# bs_shield.net
KiCad netlist of a schematic drawn in EAGLE
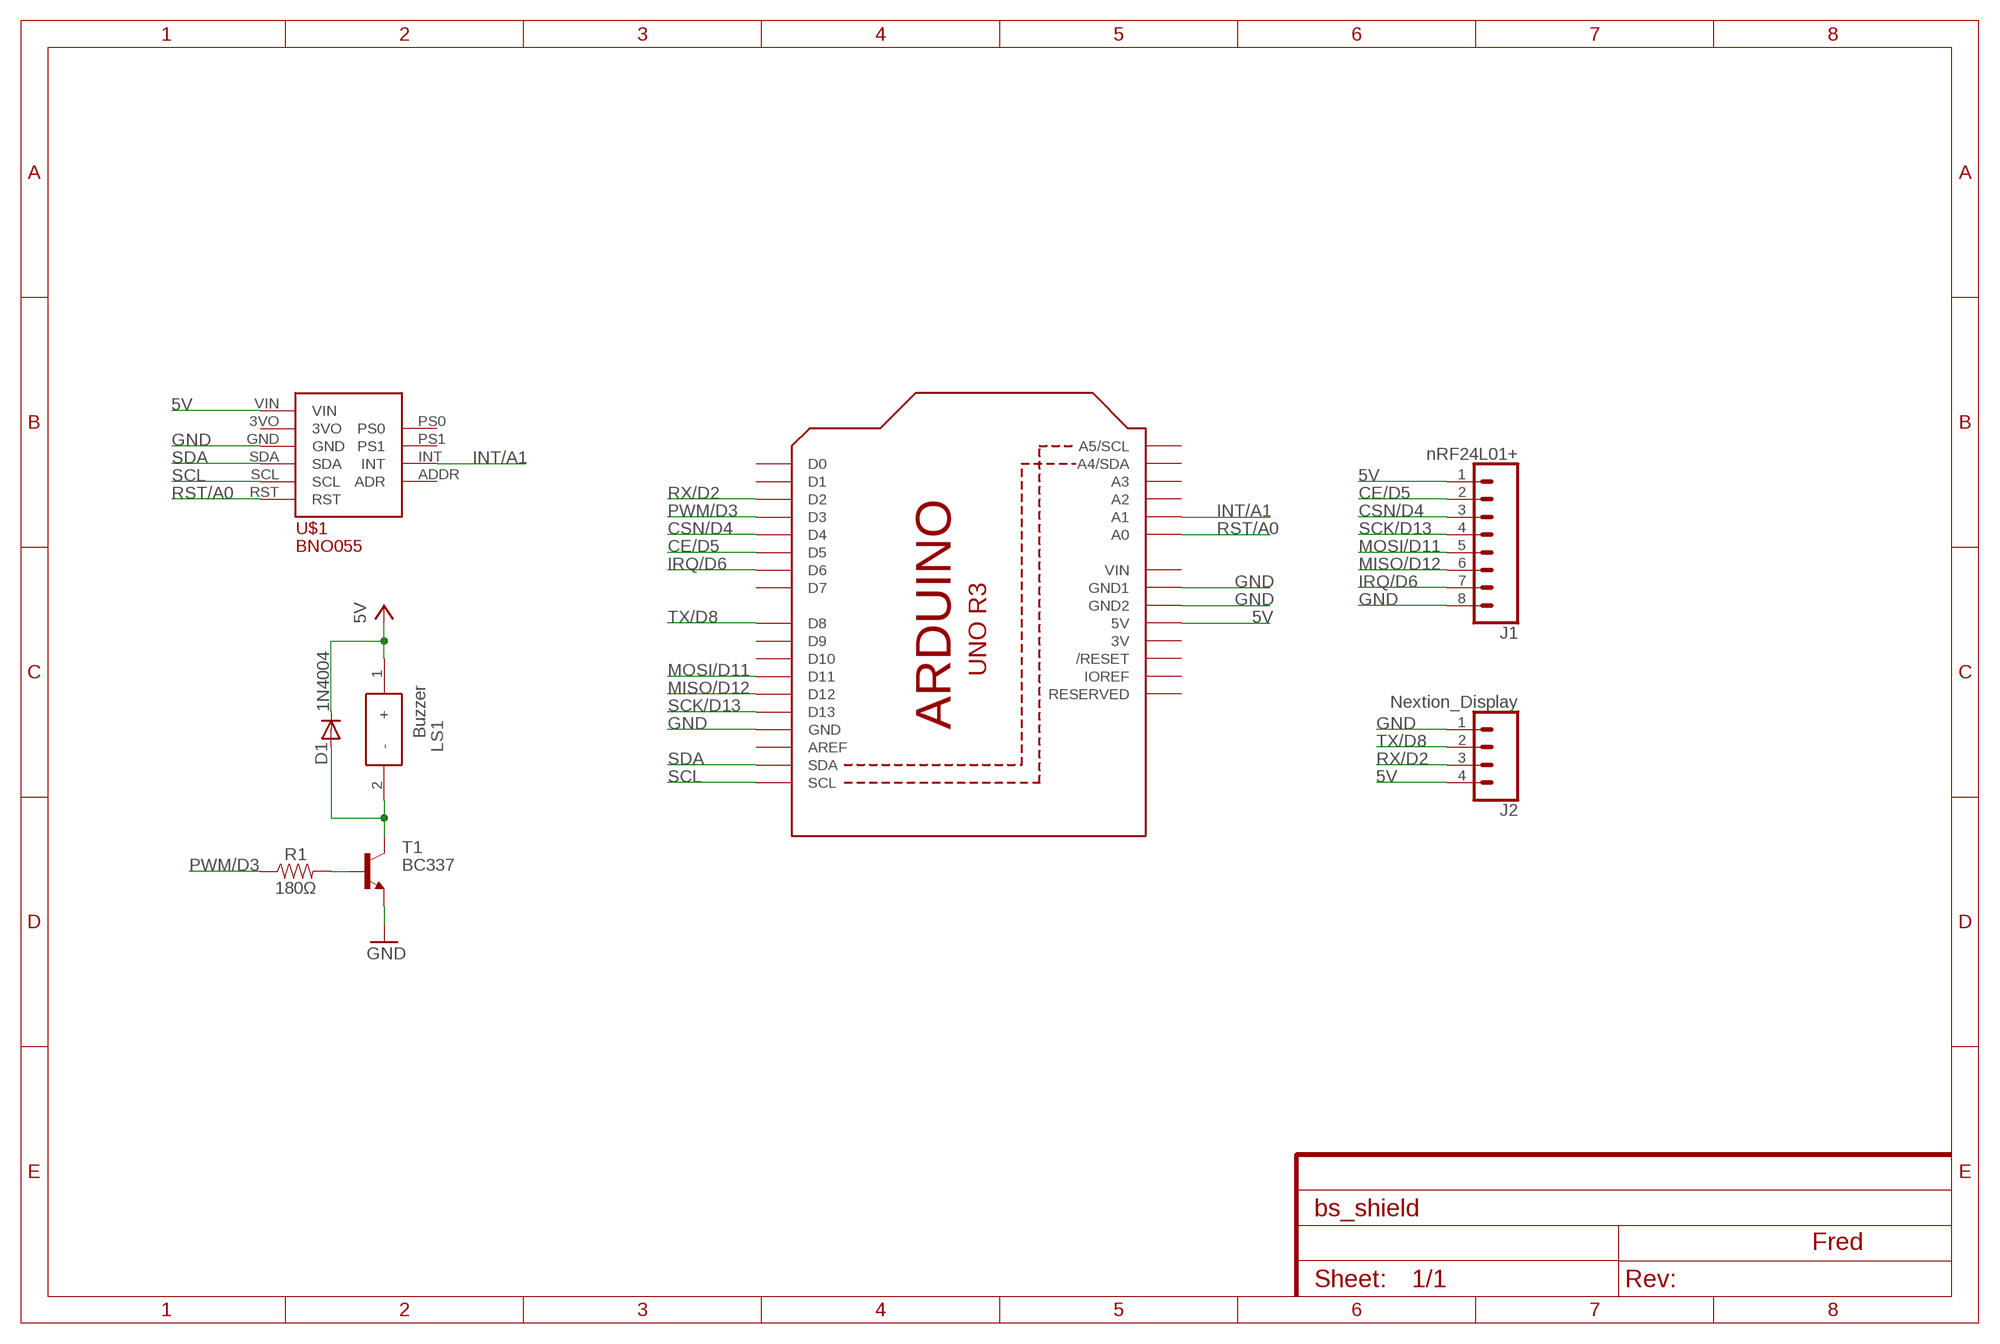
[diagram p0: schematic, sheet 1]

(export (version "E")
  (design (tool "Eeschema 10.0.6"))
  (components
    (comp (ref "D1")
      (value "1N4004")
      (footprint "eagle-import:DO41-10")
      (libsource (lib "eagle-import") (part "1N4004"))
    )
    (comp (ref "J1")
      (value "nRF24L01+")
      (footprint "eagle-import:1X08")
      (libsource (lib "eagle-import") (part "CONN_08{dblquote}"))
    )
    (comp (ref "J2")
      (value "Nextion_Display")
      (footprint "eagle-import:1X04")
      (libsource (lib "eagle-import") (part "CONN_04"))
    )
    (comp (ref "LS1")
      (value "Buzzer")
      (footprint "eagle-import:CEM-1203(42)")
      (fields
        (field (name "MANUFACTURER_PART_NUMBER") "CEM-1203(42)")
        (field (name "MOUSER_PART_NUMBER") "490-CEM-1203(42)")
      )
      (libsource (lib "eagle-import") (part "CEM-1203(42)"))
    )
    (comp (ref "R1")
      (value "180Ω")
      (footprint "eagle-import:AXIAL-0.3")
      (libsource (lib "eagle-import") (part "RESISTORAXIAL-0.3"))
    )
    (comp (ref "T1")
      (value "BC337")
      (footprint "eagle-import:TO92")
      (libsource (lib "eagle-import") (part "BC337"))
    )
    (comp (ref "U$1")
      (value "BNO055")
      (footprint "eagle-import:BB10")
      (libsource (lib "eagle-import") (part "BNO055"))
    )
    (comp (ref "U1")
      (value "ARDUINOR3-DIMENSION")
      (footprint "eagle-import:ARDUINOR3")
      (libsource (lib "eagle-import") (part "ARDUINOR3-DIMENSION"))
    )
  )
  (nets
    (net (code "1") (name "/3V") (class "Default")
      (node (ref "U1") (pin "3V") (pinfunction "3V_3V") (pintype "power_in"))
    )
    (net (code "2") (name "/CE{slash}D5") (class "Default")
      (node (ref "J1") (pin "2") (pinfunction "2_2") (pintype "passive"))
      (node (ref "U1") (pin "D5") (pinfunction "D5_D5") (pintype "bidirectional"))
    )
    (net (code "3") (name "/CSN{slash}D4") (class "Default")
      (node (ref "J1") (pin "3") (pinfunction "3_3") (pintype "passive"))
      (node (ref "U1") (pin "D4") (pinfunction "D4_D4") (pintype "bidirectional"))
    )
    (net (code "4") (name "/INT{slash}A1") (class "Default")
      (node (ref "U$1") (pin "INT") (pinfunction "INT_INT") (pintype "bidirectional"))
      (node (ref "U1") (pin "A1") (pinfunction "A1_A1") (pintype "bidirectional"))
    )
    (net (code "5") (name "/IRQ{slash}D6") (class "Default")
      (node (ref "J1") (pin "7") (pinfunction "7_7") (pintype "passive"))
      (node (ref "U1") (pin "D6") (pinfunction "D6_D6") (pintype "bidirectional"))
    )
    (net (code "6") (name "/MISO{slash}D12") (class "Default")
      (node (ref "J1") (pin "6") (pinfunction "6_6") (pintype "passive"))
      (node (ref "U1") (pin "D12") (pinfunction "D12_D12") (pintype "bidirectional"))
    )
    (net (code "7") (name "/MOSI{slash}D11") (class "Default")
      (node (ref "J1") (pin "5") (pinfunction "5_5") (pintype "passive"))
      (node (ref "U1") (pin "D11") (pinfunction "D11_D11") (pintype "bidirectional"))
    )
    (net (code "8") (name "/PWM{slash}D3") (class "Default")
      (node (ref "R1") (pin "P$1") (pinfunction "1_P$1") (pintype "passive"))
      (node (ref "U1") (pin "D3") (pinfunction "D3_D3") (pintype "bidirectional"))
    )
    (net (code "9") (name "/RST{slash}A0") (class "Default")
      (node (ref "U$1") (pin "RST") (pinfunction "RST_RST") (pintype "bidirectional"))
      (node (ref "U1") (pin "A0") (pinfunction "A0_A0") (pintype "bidirectional"))
    )
    (net (code "10") (name "/RX{slash}D2") (class "Default")
      (node (ref "J2") (pin "3") (pinfunction "3_3") (pintype "passive"))
      (node (ref "U1") (pin "D2") (pinfunction "D2_D2") (pintype "bidirectional"))
    )
    (net (code "11") (name "/SCK{slash}D13") (class "Default")
      (node (ref "J1") (pin "4") (pinfunction "4_4") (pintype "passive"))
      (node (ref "U1") (pin "D13") (pinfunction "D13_D13") (pintype "bidirectional"))
    )
    (net (code "12") (name "/SCL") (class "Default")
      (node (ref "U$1") (pin "SCL") (pinfunction "SCL_SCL") (pintype "bidirectional"))
      (node (ref "U1") (pin "SCL") (pinfunction "SCL_SCL") (pintype "bidirectional"))
    )
    (net (code "13") (name "/SDA") (class "Default")
      (node (ref "U$1") (pin "SDA") (pinfunction "SDA_SDA") (pintype "bidirectional"))
      (node (ref "U1") (pin "SDA") (pinfunction "SDA_SDA") (pintype "bidirectional"))
    )
    (net (code "14") (name "/TX{slash}D8") (class "Default")
      (node (ref "J2") (pin "2") (pinfunction "2_2") (pintype "passive"))
      (node (ref "U1") (pin "D8") (pinfunction "D8_D8") (pintype "bidirectional"))
    )
    (net (code "15") (name "/VIN") (class "Default")
      (node (ref "U1") (pin "VIN") (pinfunction "VIN_VIN") (pintype "power_in"))
    )
    (net (code "16") (name "5V") (class "Default")
      (node (ref "D1") (pin "C") (pinfunction "C_C") (pintype "passive"))
      (node (ref "J1") (pin "1") (pinfunction "1_1") (pintype "passive"))
      (node (ref "J2") (pin "4") (pinfunction "4_4") (pintype "passive"))
      (node (ref "LS1") (pin "1") (pinfunction "+_1") (pintype "bidirectional"))
      (node (ref "U$1") (pin "VIN") (pinfunction "VIN_VIN") (pintype "bidirectional"))
      (node (ref "U1") (pin "5V") (pinfunction "5V_5V") (pintype "power_in"))
    )
    (net (code "17") (name "GND") (class "Default")
      (node (ref "J1") (pin "8") (pinfunction "8_8") (pintype "passive"))
      (node (ref "J2") (pin "1") (pinfunction "1_1") (pintype "passive"))
      (node (ref "T1") (pin "1") (pinfunction "E_1") (pintype "passive"))
      (node (ref "U$1") (pin "GND") (pinfunction "GND_GND") (pintype "bidirectional"))
      (node (ref "U1") (pin "GND") (pinfunction "GND_GND") (pintype "power_in"))
      (node (ref "U1") (pin "GND1") (pinfunction "GND1_GND1") (pintype "power_in"))
      (node (ref "U1") (pin "GND2") (pinfunction "GND2_GND2") (pintype "power_in"))
    )
    (net (code "18") (name "Net-(LS1--)") (class "Default")
      (node (ref "D1") (pin "A") (pinfunction "A_A") (pintype "passive"))
      (node (ref "LS1") (pin "2") (pinfunction "-_2") (pintype "bidirectional"))
      (node (ref "T1") (pin "3") (pinfunction "C_3") (pintype "passive"))
    )
    (net (code "19") (name "Net-(R1-2)") (class "Default")
      (node (ref "R1") (pin "P$2") (pinfunction "2_P$2") (pintype "passive"))
      (node (ref "T1") (pin "2") (pinfunction "B_2") (pintype "passive"))
    )
    (net (code "20") (name "unconnected-(U$1-ADR-PadADDR)") (class "Default")
      (node (ref "U$1") (pin "ADDR") (pinfunction "ADR_ADDR") (pintype "bidirectional"))
    )
    (net (code "21") (name "unconnected-(U$1-Pad3VO)") (class "Default")
      (node (ref "U$1") (pin "3VO") (pinfunction "3VO_3VO") (pintype "bidirectional"))
    )
    (net (code "22") (name "unconnected-(U$1-PadPS0)") (class "Default")
      (node (ref "U$1") (pin "PS0") (pinfunction "PS0_PS0") (pintype "bidirectional"))
    )
    (net (code "23") (name "unconnected-(U$1-PadPS1)") (class "Default")
      (node (ref "U$1") (pin "PS1") (pinfunction "PS1_PS1") (pintype "bidirectional"))
    )
    (net (code "24") (name "unconnected-(U1-A4{slash}SDA-PadA4)") (class "Default")
      (node (ref "U1") (pin "A4") (pinfunction "A4/SDA_A4") (pintype "bidirectional"))
    )
    (net (code "25") (name "unconnected-(U1-A5{slash}SCL-PadA5)") (class "Default")
      (node (ref "U1") (pin "A5") (pinfunction "A5/SCL_A5") (pintype "bidirectional"))
    )
    (net (code "26") (name "unconnected-(U1-PadA2)") (class "Default")
      (node (ref "U1") (pin "A2") (pinfunction "A2_A2") (pintype "bidirectional"))
    )
    (net (code "27") (name "unconnected-(U1-PadA3)") (class "Default")
      (node (ref "U1") (pin "A3") (pinfunction "A3_A3") (pintype "bidirectional"))
    )
    (net (code "28") (name "unconnected-(U1-PadAREF)") (class "Default")
      (node (ref "U1") (pin "AREF") (pinfunction "AREF_AREF") (pintype "bidirectional"))
    )
    (net (code "29") (name "unconnected-(U1-PadD0)") (class "Default")
      (node (ref "U1") (pin "D0") (pinfunction "D0_D0") (pintype "bidirectional"))
    )
    (net (code "30") (name "unconnected-(U1-PadD1)") (class "Default")
      (node (ref "U1") (pin "D1") (pinfunction "D1_D1") (pintype "bidirectional"))
    )
    (net (code "31") (name "unconnected-(U1-PadD7)") (class "Default")
      (node (ref "U1") (pin "D7") (pinfunction "D7_D7") (pintype "bidirectional"))
    )
    (net (code "32") (name "unconnected-(U1-PadD9)") (class "Default")
      (node (ref "U1") (pin "D9") (pinfunction "D9_D9") (pintype "bidirectional"))
    )
    (net (code "33") (name "unconnected-(U1-PadD10)") (class "Default")
      (node (ref "U1") (pin "D10") (pinfunction "D10_D10") (pintype "bidirectional"))
    )
    (net (code "34") (name "unconnected-(U1-PadIOREF)") (class "Default")
      (node (ref "U1") (pin "IOREF") (pinfunction "IOREF_IOREF") (pintype "output"))
    )
    (net (code "35") (name "unconnected-(U1-PadRESERVED)") (class "Default")
      (node (ref "U1") (pin "RESERVED") (pinfunction "RESERVED_RESERVED") (pintype "no_connect"))
    )
    (net (code "36") (name "unconnected-(U1-{slash}RESET-PadRESET)") (class "Default")
      (node (ref "U1") (pin "RESET") (pinfunction "/RESET_RESET") (pintype "bidirectional"))
    )
  )
)
